# MainBoard_USB.net
KiCad netlist of a schematic drawn in Altium Designer
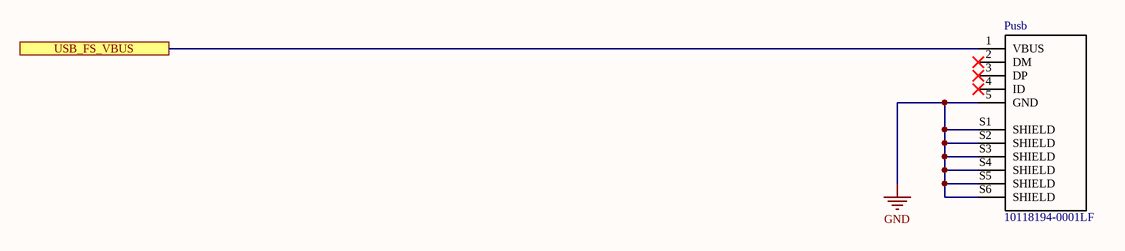
[diagram p0: MainBoard_USB.SchDoc]

(export (version "E")
  (design (tool "Eeschema 10.0.6"))
  (components
    (comp (ref "Pusb")
      (value "10118194-0001LF")
      (footprint "USB Micro B Receptacle")
      (description "USB - micro B USB 2.0 Receptacle Connector 5 Position Surface Mount, Right Angle; Through Hole")
      (fields (field (name "MF") "Amphenol ICC (FCI)"))
      (libsource (lib "AltiumLibraries") (part "USB Micro B Receptacle"))
    )
  )
  (nets
    (net (code "1") (name "/USB_FS_VBUS") (class "Default")
      (node (ref "Pusb") (pin "1") (pinfunction "VBUS_1") (pintype "passive"))
    )
    (net (code "2") (name "GND") (class "Default")
      (node (ref "Pusb") (pin "5") (pinfunction "GND_5") (pintype "passive"))
      (node (ref "Pusb") (pin "S1") (pinfunction "SHIELD_S1") (pintype "passive"))
      (node (ref "Pusb") (pin "S2") (pinfunction "SHIELD_S2") (pintype "passive"))
      (node (ref "Pusb") (pin "S3") (pinfunction "SHIELD_S3") (pintype "passive"))
      (node (ref "Pusb") (pin "S4") (pinfunction "SHIELD_S4") (pintype "passive"))
      (node (ref "Pusb") (pin "S5") (pinfunction "SHIELD_S5") (pintype "passive"))
      (node (ref "Pusb") (pin "S6") (pinfunction "SHIELD_S6") (pintype "passive"))
    )
    (net (code "3") (name "unconnected-(Pusb-DM-Pad2)") (class "Default")
      (node (ref "Pusb") (pin "2") (pinfunction "DM_2") (pintype "passive+no_connect"))
    )
    (net (code "4") (name "unconnected-(Pusb-DP-Pad3)") (class "Default")
      (node (ref "Pusb") (pin "3") (pinfunction "DP_3") (pintype "passive+no_connect"))
    )
    (net (code "5") (name "unconnected-(Pusb-ID-Pad4)") (class "Default")
      (node (ref "Pusb") (pin "4") (pinfunction "ID_4") (pintype "passive+no_connect"))
    )
  )
)
